# Sheet1.net
KiCad netlist of a schematic drawn in Altium Designer
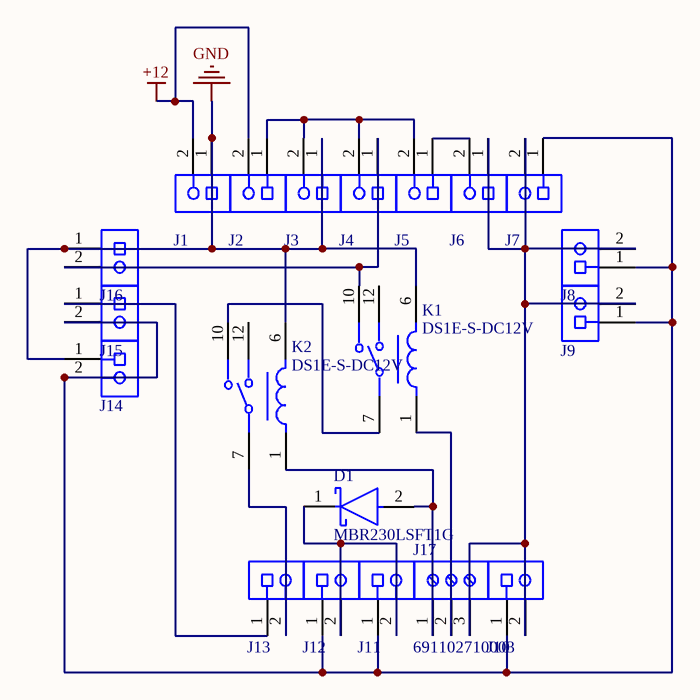
[diagram p0: Sheet1.SchDoc]

(export (version "E")
  (design (tool "Eeschema 10.0.6"))
  (components
    (comp (ref "D1")
      (value "MBR230LSFT1G")
      (footprint "FP-498-MFG")
      (description "DIODE SCHOTTKY 30V 2A SOD123L")
      (libsource (lib "Altium Content Vault") (part "1d6ec82d83fb6aee721767c19dac4b9"))
    )
    (comp (ref "J1")
      (value "1729128")
      (footprint "PHOE-1729128-2_V")
      (description "PCB Terminal Block, 13.5 A, 400 V, 2-Pin THD, RoHS, Bulk")
      (fields (field (name "MANUFACTURER") "Phoenix Contact"))
      (libsource (lib "") (part "CN-2P-F-R2_2"))
    )
    (comp (ref "J2")
      (value "1729128")
      (footprint "PHOE-1729128-2_V")
      (description "PCB Terminal Block, 13.5 A, 400 V, 2-Pin THD, RoHS, Bulk")
      (fields (field (name "MANUFACTURER") "Phoenix Contact"))
      (libsource (lib "") (part "CN-2P-F-R2_2"))
    )
    (comp (ref "J3")
      (value "1729128")
      (footprint "PHOE-1729128-2_V")
      (description "PCB Terminal Block, 13.5 A, 400 V, 2-Pin THD, RoHS, Bulk")
      (fields (field (name "MANUFACTURER") "Phoenix Contact"))
      (libsource (lib "") (part "CN-2P-F-R2_2"))
    )
    (comp (ref "J4")
      (value "1729128")
      (footprint "PHOE-1729128-2_V")
      (description "PCB Terminal Block, 13.5 A, 400 V, 2-Pin THD, RoHS, Bulk")
      (fields (field (name "MANUFACTURER") "Phoenix Contact"))
      (libsource (lib "") (part "CN-2P-F-R2_2"))
    )
    (comp (ref "J5")
      (value "1729128")
      (footprint "PHOE-1729128-2_V")
      (description "PCB Terminal Block, 13.5 A, 400 V, 2-Pin THD, RoHS, Bulk")
      (fields (field (name "MANUFACTURER") "Phoenix Contact"))
      (libsource (lib "") (part "CN-2P-F-R2_2"))
    )
    (comp (ref "J6")
      (value "1729128")
      (footprint "PHOE-1729128-2_V")
      (description "PCB Terminal Block, 13.5 A, 400 V, 2-Pin THD, RoHS, Bulk")
      (fields (field (name "MANUFACTURER") "Phoenix Contact"))
      (libsource (lib "") (part "CN-2P-F-R2_2"))
    )
    (comp (ref "J7")
      (value "1729128")
      (footprint "PHOE-1729128-2_V")
      (description "PCB Terminal Block, 13.5 A, 400 V, 2-Pin THD, RoHS, Bulk")
      (fields (field (name "MANUFACTURER") "Phoenix Contact"))
      (libsource (lib "") (part "CN-2P-F-R2_2"))
    )
    (comp (ref "J8")
      (value "1729128")
      (footprint "PHOE-1729128-2_V")
      (description "PCB Terminal Block, 13.5 A, 400 V, 2-Pin THD, RoHS, Bulk")
      (fields (field (name "MANUFACTURER") "Phoenix Contact"))
      (libsource (lib "") (part "CN-2P-F-R2_3"))
    )
    (comp (ref "J9")
      (value "1729128")
      (footprint "PHOE-1729128-2_V")
      (description "PCB Terminal Block, 13.5 A, 400 V, 2-Pin THD, RoHS, Bulk")
      (fields (field (name "MANUFACTURER") "Phoenix Contact"))
      (libsource (lib "") (part "CN-2P-F-R2_3"))
    )
    (comp (ref "J10")
      (value "1729128")
      (footprint "PHOE-1729128-2_V")
      (description "PCB Terminal Block, 13.5 A, 400 V, 2-Pin THD, RoHS, Bulk")
      (fields (field (name "MANUFACTURER") "Phoenix Contact"))
      (libsource (lib "Altium Content Vault") (part "CN-2P-F-R2"))
    )
    (comp (ref "J11")
      (value "1729128")
      (footprint "PHOE-1729128-2_V")
      (description "PCB Terminal Block, 13.5 A, 400 V, 2-Pin THD, RoHS, Bulk")
      (fields (field (name "MANUFACTURER") "Phoenix Contact"))
      (libsource (lib "Altium Content Vault") (part "CN-2P-F-R2"))
    )
    (comp (ref "J12")
      (value "1729128")
      (footprint "PHOE-1729128-2_V")
      (description "PCB Terminal Block, 13.5 A, 400 V, 2-Pin THD, RoHS, Bulk")
      (fields (field (name "MANUFACTURER") "Phoenix Contact"))
      (libsource (lib "Altium Content Vault") (part "CN-2P-F-R2"))
    )
    (comp (ref "J13")
      (value "1729128")
      (footprint "PHOE-1729128-2_V")
      (description "PCB Terminal Block, 13.5 A, 400 V, 2-Pin THD, RoHS, Bulk")
      (fields (field (name "MANUFACTURER") "Phoenix Contact"))
      (libsource (lib "Altium Content Vault") (part "CN-2P-F-R2"))
    )
    (comp (ref "J14")
      (value "1729128")
      (footprint "PHOE-1729128-2_V")
      (description "PCB Terminal Block, 13.5 A, 400 V, 2-Pin THD, RoHS, Bulk")
      (fields (field (name "MANUFACTURER") "Phoenix Contact"))
      (libsource (lib "") (part "CN-2P-F-R2_1"))
    )
    (comp (ref "J15")
      (value "1729128")
      (footprint "PHOE-1729128-2_V")
      (description "PCB Terminal Block, 13.5 A, 400 V, 2-Pin THD, RoHS, Bulk")
      (fields (field (name "MANUFACTURER") "Phoenix Contact"))
      (libsource (lib "") (part "CN-2P-F-R2_1"))
    )
    (comp (ref "J16")
      (value "1729128")
      (footprint "PHOE-1729128-2_V")
      (description "PCB Terminal Block, 13.5 A, 400 V, 2-Pin THD, RoHS, Bulk")
      (fields (field (name "MANUFACTURER") "Phoenix Contact"))
      (libsource (lib "") (part "CN-2P-F-R2_1"))
    )
    (comp (ref "J17")
      (value "691102710003")
      (footprint "691102710003")
      (fields (field (name "VOLTAGE") "300V"))
      (libsource (lib "Altium Content Vault") (part "TBL - 1R - 03P - Screw"))
    )
    (comp (ref "K1")
      (value "DS1E-S-DC12V")
      (footprint "FP-DS1E-S-DC12V-MFG")
      (description "DS1E-S-DC12V Relay; 2 A AC/DC (Switching), 3 A AC/DC (Carrying); Amber Sealed Type; 1 Form C")
      (libsource (lib "Altium Content Vault") (part "270cc5822e726e537db2ab9d0a52a17"))
    )
    (comp (ref "K2")
      (value "DS1E-S-DC12V")
      (footprint "FP-DS1E-S-DC12V-MFG")
      (description "DS1E-S-DC12V Relay; 2 A AC/DC (Switching), 3 A AC/DC (Carrying); Amber Sealed Type; 1 Form C")
      (libsource (lib "Altium Content Vault") (part "270cc5822e726e537db2ab9d0a52a17"))
    )
  )
  (nets
    (net (code "1") (name "+12") (class "Default")
      (node (ref "J1") (pin "2") (pinfunction "2_2") (pintype "passive"))
      (node (ref "J2") (pin "2") (pinfunction "2_2") (pintype "passive"))
    )
    (net (code "2") (name "GND") (class "Default")
      (node (ref "J1") (pin "1") (pinfunction "1_1") (pintype "passive"))
      (node (ref "J14") (pin "1") (pinfunction "1_1") (pintype "passive"))
      (node (ref "J16") (pin "1") (pinfunction "1_1") (pintype "passive"))
      (node (ref "J3") (pin "1") (pinfunction "1_1") (pintype "passive"))
      (node (ref "K1") (pin "6") (pinfunction "-_6") (pintype "passive"))
      (node (ref "K2") (pin "6") (pinfunction "-_6") (pintype "passive"))
    )
    (net (code "3") (name "Net-(D1-A)") (class "Default")
      (node (ref "D1") (pin "2") (pinfunction "A_2") (pintype "passive"))
      (node (ref "J17") (pin "1") (pinfunction "1_1") (pintype "passive"))
      (node (ref "K2") (pin "1") (pinfunction "+_1") (pintype "passive"))
    )
    (net (code "4") (name "Net-(D1-C)") (class "Default")
      (node (ref "D1") (pin "1") (pinfunction "C_1") (pintype "passive"))
      (node (ref "J11") (pin "2") (pinfunction "2_2") (pintype "passive"))
      (node (ref "J12") (pin "2") (pinfunction "2_2") (pintype "passive"))
    )
    (net (code "5") (name "Net-(J2-Pad1)") (class "Default")
      (node (ref "J2") (pin "1") (pinfunction "1_1") (pintype "passive"))
      (node (ref "J3") (pin "2") (pinfunction "2_2") (pintype "passive"))
      (node (ref "J4") (pin "2") (pinfunction "2_2") (pintype "passive"))
      (node (ref "J5") (pin "2") (pinfunction "2_2") (pintype "passive"))
    )
    (net (code "6") (name "Net-(J5-Pad1)") (class "Default")
      (node (ref "J5") (pin "1") (pinfunction "1_1") (pintype "passive"))
      (node (ref "J6") (pin "2") (pinfunction "2_2") (pintype "passive"))
    )
    (net (code "7") (name "Net-(J10-Pad1)") (class "Default")
      (node (ref "J10") (pin "1") (pinfunction "1_1") (pintype "passive"))
      (node (ref "J11") (pin "1") (pinfunction "1_1") (pintype "passive"))
      (node (ref "J12") (pin "1") (pinfunction "1_1") (pintype "passive"))
      (node (ref "J14") (pin "2") (pinfunction "2_2") (pintype "passive"))
      (node (ref "J15") (pin "2") (pinfunction "2_2") (pintype "passive"))
      (node (ref "J7") (pin "1") (pinfunction "1_1") (pintype "passive"))
      (node (ref "J8") (pin "1") (pinfunction "1_1") (pintype "passive"))
      (node (ref "J9") (pin "1") (pinfunction "1_1") (pintype "passive"))
    )
    (net (code "8") (name "Net-(J10-Pad2)") (class "Default")
      (node (ref "J10") (pin "2") (pinfunction "2_2") (pintype "passive"))
      (node (ref "J17") (pin "3") (pinfunction "3_3") (pintype "passive"))
      (node (ref "J6") (pin "1") (pinfunction "1_1") (pintype "passive"))
      (node (ref "J7") (pin "2") (pinfunction "2_2") (pintype "passive"))
      (node (ref "J8") (pin "2") (pinfunction "2_2") (pintype "passive"))
      (node (ref "J9") (pin "2") (pinfunction "2_2") (pintype "passive"))
    )
    (net (code "9") (name "Net-(J13-Pad1)") (class "Default")
      (node (ref "J13") (pin "1") (pinfunction "1_1") (pintype "passive"))
      (node (ref "J15") (pin "1") (pinfunction "1_1") (pintype "passive"))
    )
    (net (code "10") (name "Net-(K1-+)") (class "Default")
      (node (ref "J17") (pin "2") (pinfunction "2_2") (pintype "passive"))
      (node (ref "K1") (pin "1") (pinfunction "+_1") (pintype "passive"))
    )
    (net (code "11") (name "Net-(K1-COM)") (class "Default")
      (node (ref "K1") (pin "7") (pinfunction "COM_7") (pintype "passive"))
      (node (ref "K2") (pin "10") (pinfunction "N.C._10") (pintype "passive"))
    )
    (net (code "12") (name "Net-(K1-N.C.)") (class "Default")
      (node (ref "J16") (pin "2") (pinfunction "2_2") (pintype "passive"))
      (node (ref "J4") (pin "1") (pinfunction "1_1") (pintype "passive"))
      (node (ref "K1") (pin "10") (pinfunction "N.C._10") (pintype "passive"))
    )
    (net (code "13") (name "Net-(K2-COM)") (class "Default")
      (node (ref "J13") (pin "2") (pinfunction "2_2") (pintype "passive"))
      (node (ref "K2") (pin "7") (pinfunction "COM_7") (pintype "passive"))
    )
    (net (code "14") (name "unconnected-(K1-N.O.-Pad12)") (class "Default")
      (node (ref "K1") (pin "12") (pinfunction "N.O._12") (pintype "passive"))
    )
    (net (code "15") (name "unconnected-(K2-N.O.-Pad12)") (class "Default")
      (node (ref "K2") (pin "12") (pinfunction "N.O._12") (pintype "passive"))
    )
  )
)
